# Digital.net
KiCad netlist of a schematic drawn in Altium Designer
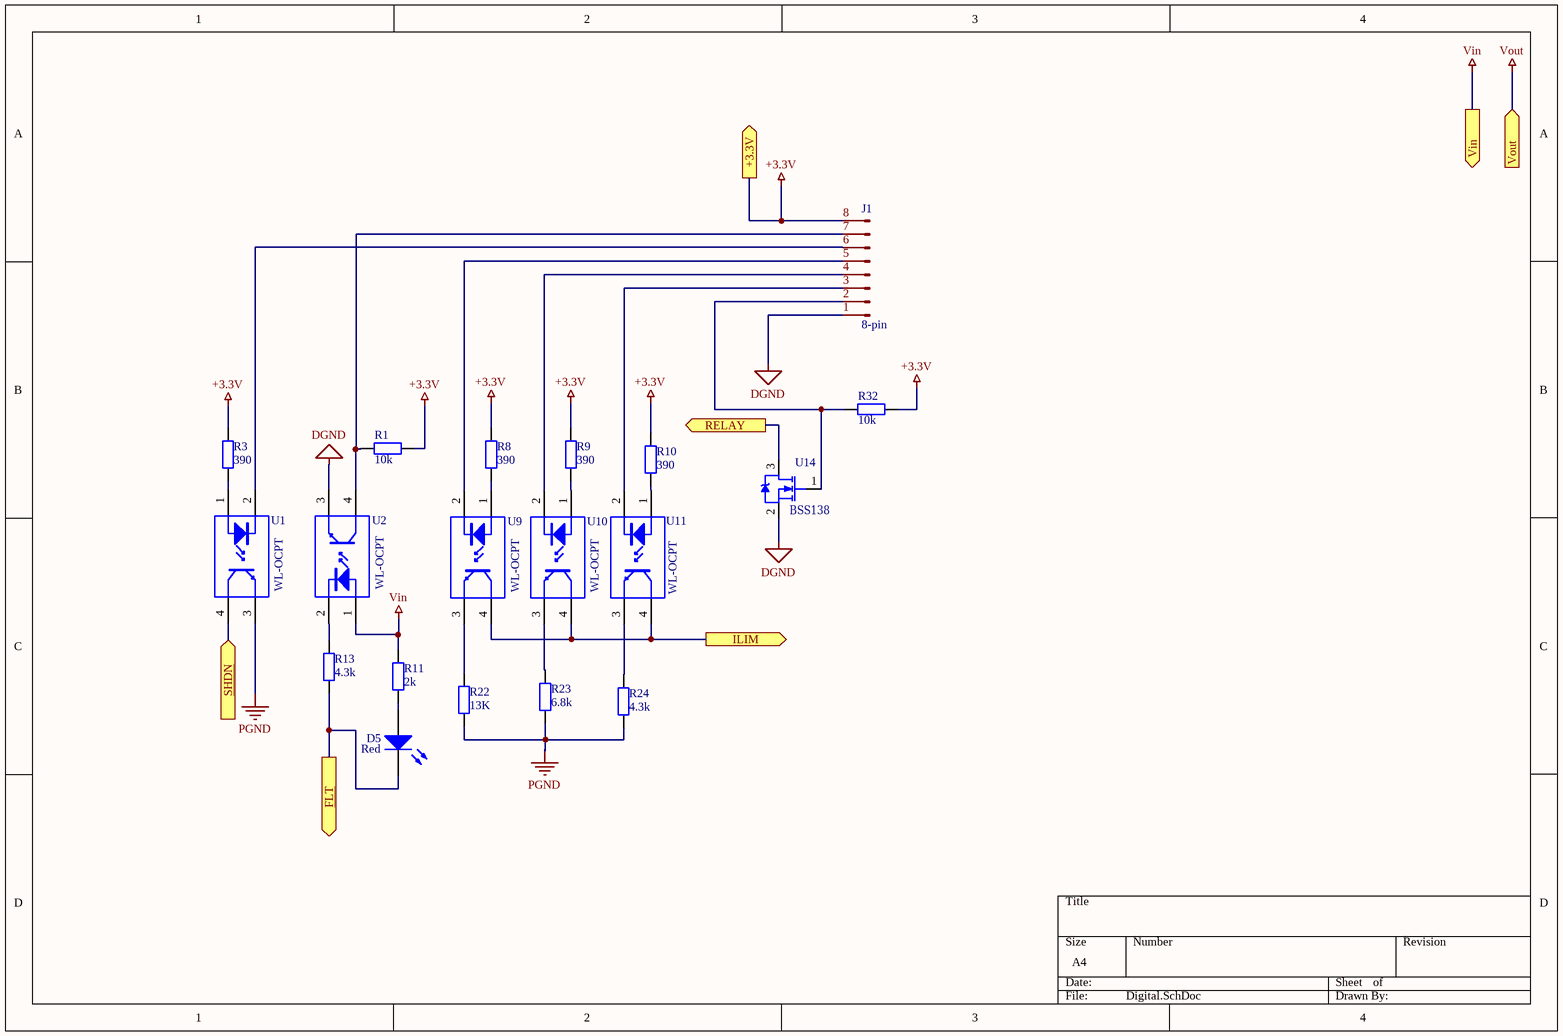
[diagram p0: Digital.SchDoc]

(export (version "E")
  (design (tool "Eeschema 10.0.6"))
  (components
    (comp (ref "D5") (value "Red") (footprint "0805 LED") (libsource (lib "generic_components") (part "LED")))
    (comp (ref "J1")
      (value "8-pin")
      (footprint "JST_XH_B8B-XH-A_1x08_P2.50mm_Vertical")
      (libsource (lib "JST") (part "8-pin"))
    )
    (comp (ref "R1") (value "10k") (footprint "0805") (libsource (lib "") (part "res0805_2")))
    (comp (ref "R3") (value "390") (footprint "0805") (libsource (lib "generic_components") (part "res0805")))
    (comp (ref "R8") (value "390") (footprint "0805") (libsource (lib "generic_components") (part "res0805")))
    (comp (ref "R9") (value "390") (footprint "0805") (libsource (lib "generic_components") (part "res0805")))
    (comp (ref "R10")
      (value "390")
      (footprint "0805")
      (libsource (lib "generic_components") (part "res0805"))
    )
    (comp (ref "R11") (value "2k") (footprint "0805") (libsource (lib "generic_components") (part "res0805")))
    (comp (ref "R13")
      (value "4.3k")
      (footprint "0805")
      (libsource (lib "generic_components") (part "res0805"))
    )
    (comp (ref "R22")
      (value "13K")
      (footprint "0805")
      (libsource (lib "generic_components") (part "res0805"))
    )
    (comp (ref "R23")
      (value "6.8k")
      (footprint "0805")
      (libsource (lib "generic_components") (part "res0805"))
    )
    (comp (ref "R24")
      (value "4.3k")
      (footprint "0805")
      (libsource (lib "generic_components") (part "res0805"))
    )
    (comp (ref "R32") (value "10k") (footprint "0805") (libsource (lib "") (part "res0805_1")))
    (comp (ref "U1")
      (value "WL-OCPT")
      (footprint "4-SOP_WE_opto-isolator")
      (libsource (lib "generic_components") (part "optoc WE"))
    )
    (comp (ref "U2")
      (value "WL-OCPT")
      (footprint "4-SOP_WE_opto-isolator")
      (libsource (lib "generic_components") (part "optoc WE"))
    )
    (comp (ref "U9")
      (value "WL-OCPT")
      (footprint "4-SOP_WE_opto-isolator")
      (libsource (lib "generic_components") (part "optoc WE"))
    )
    (comp (ref "U10")
      (value "WL-OCPT")
      (footprint "4-SOP_WE_opto-isolator")
      (libsource (lib "generic_components") (part "optoc WE"))
    )
    (comp (ref "U11")
      (value "WL-OCPT")
      (footprint "4-SOP_WE_opto-isolator")
      (libsource (lib "generic_components") (part "optoc WE"))
    )
    (comp (ref "U14")
      (value "BSS138‎")
      (footprint "SOT-23-3")
      (libsource (lib "generic_components") (part "N-mosfet en"))
    )
  )
  (nets
    (net (code "1") (name "+3.3V") (class "Default")
      (node (ref "J1") (pin "8") (pinfunction "Pin_8_8") (pintype "passive"))
      (node (ref "R1") (pin "1") (pintype "passive"))
      (node (ref "R10") (pin "2") (pinfunction "2_2") (pintype "passive"))
      (node (ref "R3") (pin "2") (pinfunction "2_2") (pintype "passive"))
      (node (ref "R32") (pin "2") (pinfunction "2_2") (pintype "passive"))
      (node (ref "R8") (pin "2") (pinfunction "2_2") (pintype "passive"))
      (node (ref "R9") (pin "2") (pinfunction "2_2") (pintype "passive"))
    )
    (net (code "2") (name "/FLT") (class "Default")
      (node (ref "D5") (pin "1") (pinfunction "K_1") (pintype "passive"))
      (node (ref "R13") (pin "1") (pintype "passive"))
    )
    (net (code "3") (name "/ILIM") (class "Default")
      (node (ref "U10") (pin "4") (pinfunction "C_4") (pintype "passive"))
      (node (ref "U11") (pin "4") (pinfunction "C_4") (pintype "passive"))
      (node (ref "U9") (pin "4") (pinfunction "C_4") (pintype "passive"))
    )
    (net (code "4") (name "/RELAY") (class "Default")
      (node (ref "U14") (pin "3") (pinfunction "S_3") (pintype "passive"))
    )
    (net (code "5") (name "/SHDN") (class "Default")
      (node (ref "U1") (pin "4") (pinfunction "C_4") (pintype "passive"))
    )
    (net (code "6") (name "DGND") (class "Default")
      (node (ref "J1") (pin "1") (pinfunction "Pin_1_1") (pintype "passive"))
      (node (ref "U14") (pin "2") (pinfunction "D_2") (pintype "passive"))
      (node (ref "U2") (pin "3") (pinfunction "E_3") (pintype "passive"))
    )
    (net (code "7") (name "Net-(D5-A)") (class "Default")
      (node (ref "D5") (pin "2") (pinfunction "A_2") (pintype "passive"))
      (node (ref "R11") (pin "1") (pintype "passive"))
    )
    (net (code "8") (name "Net-(J1-Pin_2)") (class "Default")
      (node (ref "J1") (pin "2") (pinfunction "Pin_2_2") (pintype "passive"))
      (node (ref "R32") (pin "1") (pintype "passive"))
      (node (ref "U14") (pin "1") (pinfunction "G_1") (pintype "passive"))
    )
    (net (code "9") (name "Net-(J1-Pin_3)") (class "Default")
      (node (ref "J1") (pin "3") (pinfunction "Pin_3_3") (pintype "passive"))
      (node (ref "U11") (pin "2") (pinfunction "C_2") (pintype "passive"))
    )
    (net (code "10") (name "Net-(J1-Pin_4)") (class "Default")
      (node (ref "J1") (pin "4") (pinfunction "Pin_4_4") (pintype "passive"))
      (node (ref "U10") (pin "2") (pinfunction "C_2") (pintype "passive"))
    )
    (net (code "11") (name "Net-(J1-Pin_5)") (class "Default")
      (node (ref "J1") (pin "5") (pinfunction "Pin_5_5") (pintype "passive"))
      (node (ref "U9") (pin "2") (pinfunction "C_2") (pintype "passive"))
    )
    (net (code "12") (name "Net-(J1-Pin_6)") (class "Default")
      (node (ref "J1") (pin "6") (pinfunction "Pin_6_6") (pintype "passive"))
      (node (ref "U1") (pin "2") (pinfunction "C_2") (pintype "passive"))
    )
    (net (code "13") (name "Net-(J1-Pin_7)") (class "Default")
      (node (ref "J1") (pin "7") (pinfunction "Pin_7_7") (pintype "passive"))
      (node (ref "R1") (pin "2") (pinfunction "2_2") (pintype "passive"))
      (node (ref "U2") (pin "4") (pinfunction "C_4") (pintype "passive"))
    )
    (net (code "14") (name "Net-(R13-Pad2)") (class "Default")
      (node (ref "R13") (pin "2") (pinfunction "2_2") (pintype "passive"))
      (node (ref "U2") (pin "2") (pinfunction "C_2") (pintype "passive"))
    )
    (net (code "15") (name "Net-(U1-A)") (class "Default")
      (node (ref "R3") (pin "1") (pintype "passive"))
      (node (ref "U1") (pin "1") (pinfunction "A_1") (pintype "passive"))
    )
    (net (code "16") (name "Net-(U9-A)") (class "Default")
      (node (ref "R8") (pin "1") (pintype "passive"))
      (node (ref "U9") (pin "1") (pinfunction "A_1") (pintype "passive"))
    )
    (net (code "17") (name "Net-(U9-E)") (class "Default")
      (node (ref "R22") (pin "2") (pinfunction "2_2") (pintype "passive"))
      (node (ref "U9") (pin "3") (pinfunction "E_3") (pintype "passive"))
    )
    (net (code "18") (name "Net-(U10-A)") (class "Default")
      (node (ref "R9") (pin "1") (pintype "passive"))
      (node (ref "U10") (pin "1") (pinfunction "A_1") (pintype "passive"))
    )
    (net (code "19") (name "Net-(U10-E)") (class "Default")
      (node (ref "R23") (pin "2") (pinfunction "2_2") (pintype "passive"))
      (node (ref "U10") (pin "3") (pinfunction "E_3") (pintype "passive"))
    )
    (net (code "20") (name "Net-(U11-A)") (class "Default")
      (node (ref "R10") (pin "1") (pintype "passive"))
      (node (ref "U11") (pin "1") (pinfunction "A_1") (pintype "passive"))
    )
    (net (code "21") (name "Net-(U11-E)") (class "Default")
      (node (ref "R24") (pin "2") (pinfunction "2_2") (pintype "passive"))
      (node (ref "U11") (pin "3") (pinfunction "E_3") (pintype "passive"))
    )
    (net (code "22") (name "PGND") (class "Default")
      (node (ref "R22") (pin "1") (pintype "passive"))
      (node (ref "R23") (pin "1") (pintype "passive"))
      (node (ref "R24") (pin "1") (pintype "passive"))
      (node (ref "U1") (pin "3") (pinfunction "E_3") (pintype "passive"))
    )
    (net (code "23") (name "Vin") (class "Default")
      (node (ref "R11") (pin "2") (pinfunction "2_2") (pintype "passive"))
      (node (ref "U2") (pin "1") (pinfunction "A_1") (pintype "passive"))
    )
  )
)
